# wifi.net
KiCad netlist of a schematic drawn in EAGLE
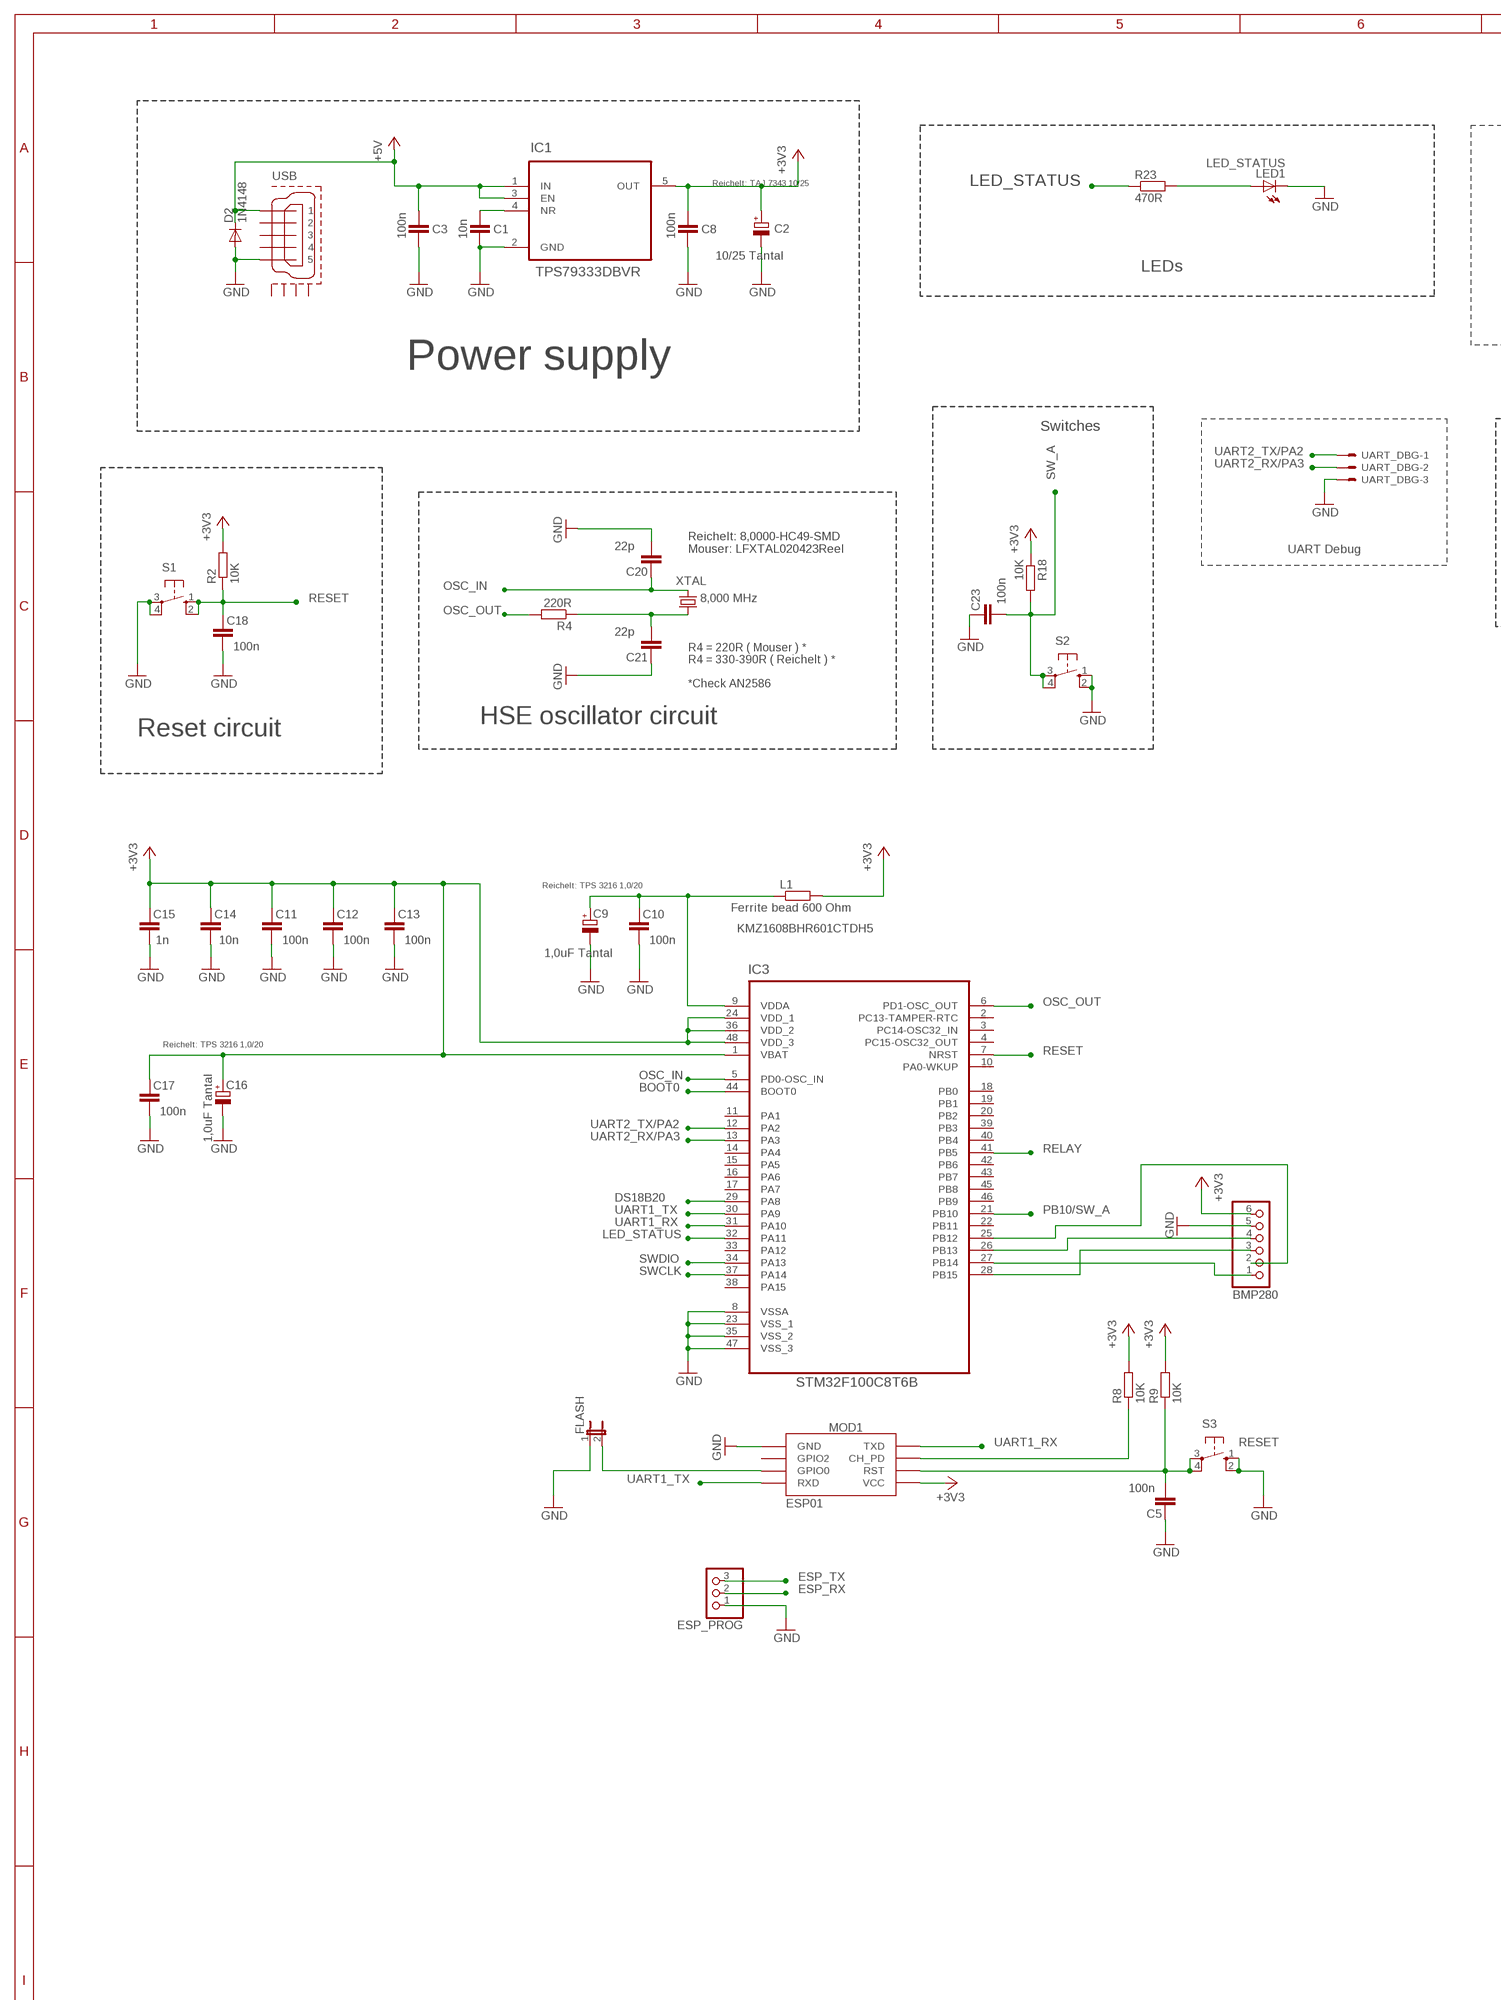
[diagram p0: schematic, sheet 1, part 1 of 2]
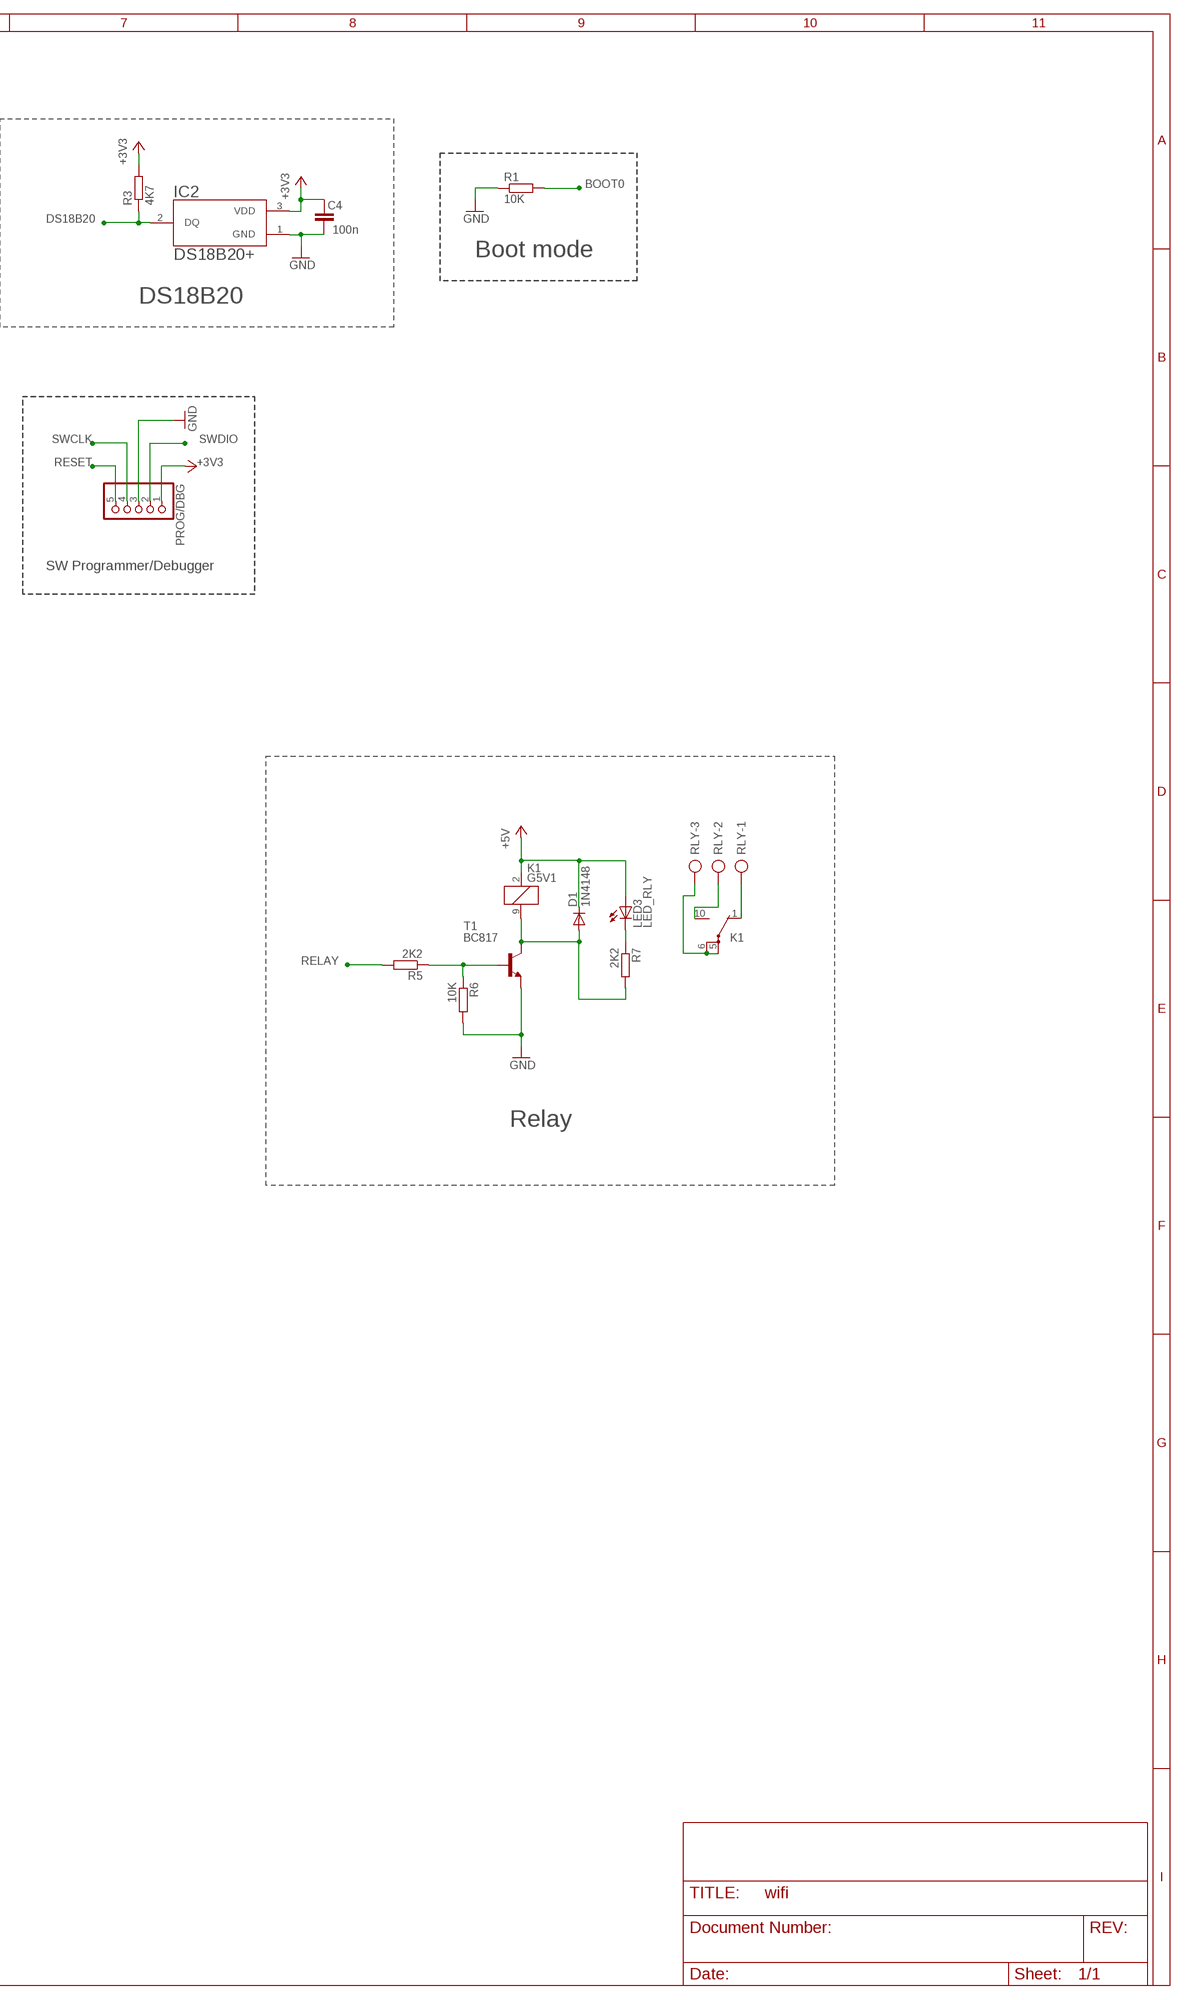
[diagram p1: schematic, sheet 1, part 2 of 2]

(export (version "E")
  (design (tool "Eeschema 10.0.6"))
  (components
    (comp (ref "BMP280")
      (value "PINHD-1X6")
      (footprint "eagle-import:1X06")
      (libsource (lib "eagle-import") (part "PINHD-1X6"))
    )
    (comp (ref "C1")
      (value "10n")
      (footprint "eagle-import:C0805")
      (libsource (lib "eagle-import") (part "C-EUC0805"))
    )
    (comp (ref "C2")
      (value "10/25 Tantal")
      (footprint "eagle-import:SMC_D")
      (libsource (lib "eagle-import") (part "CPOL-EUSMCD"))
    )
    (comp (ref "C3")
      (value "100n")
      (footprint "eagle-import:C0805")
      (libsource (lib "eagle-import") (part "C-EUC0805"))
    )
    (comp (ref "C4")
      (value "100n")
      (footprint "eagle-import:C0805")
      (libsource (lib "eagle-import") (part "C-EUC0805"))
    )
    (comp (ref "C5")
      (value "100n")
      (footprint "eagle-import:C0805")
      (libsource (lib "eagle-import") (part "C-EUC0805"))
    )
    (comp (ref "C8")
      (value "100n")
      (footprint "eagle-import:C0805")
      (libsource (lib "eagle-import") (part "C-EUC0805"))
    )
    (comp (ref "C9")
      (value "1,0uF Tantal")
      (footprint "eagle-import:SMC_A")
      (libsource (lib "eagle-import") (part "CPOL-EUSMCA"))
    )
    (comp (ref "C10")
      (value "100n")
      (footprint "eagle-import:C0402K")
      (libsource (lib "eagle-import") (part "C-EUC0402K"))
    )
    (comp (ref "C11")
      (value "100n")
      (footprint "eagle-import:C0402K")
      (libsource (lib "eagle-import") (part "C-EUC0402K"))
    )
    (comp (ref "C12")
      (value "100n")
      (footprint "eagle-import:C0402K")
      (libsource (lib "eagle-import") (part "C-EUC0402K"))
    )
    (comp (ref "C13")
      (value "100n")
      (footprint "eagle-import:C0402K")
      (libsource (lib "eagle-import") (part "C-EUC0402K"))
    )
    (comp (ref "C14")
      (value "10n")
      (footprint "eagle-import:C0402K")
      (libsource (lib "eagle-import") (part "C-EUC0402K"))
    )
    (comp (ref "C15")
      (value "1n")
      (footprint "eagle-import:C0402K")
      (libsource (lib "eagle-import") (part "C-EUC0402K"))
    )
    (comp (ref "C16")
      (value "1,0uF Tantal")
      (footprint "eagle-import:SMC_A")
      (libsource (lib "eagle-import") (part "CPOL-EUSMCA"))
    )
    (comp (ref "C17")
      (value "100n")
      (footprint "eagle-import:C0402K")
      (libsource (lib "eagle-import") (part "C-EUC0402K"))
    )
    (comp (ref "C18")
      (value "100n")
      (footprint "eagle-import:C0603K")
      (libsource (lib "eagle-import") (part "C-EUC0603K"))
    )
    (comp (ref "C20")
      (value "22p")
      (footprint "eagle-import:C0603K")
      (libsource (lib "eagle-import") (part "C-EUC0603K"))
    )
    (comp (ref "C21")
      (value "22p")
      (footprint "eagle-import:C0603K")
      (libsource (lib "eagle-import") (part "C-EUC0603K"))
    )
    (comp (ref "C23")
      (value "100n")
      (footprint "eagle-import:C0805")
      (libsource (lib "eagle-import") (part "C-EUC0805"))
    )
    (comp (ref "D1")
      (value "1N4148")
      (footprint "eagle-import:DO35-7")
      (libsource (lib "eagle-import") (part "1N4148DO35-7"))
    )
    (comp (ref "D2")
      (value "1N4148")
      (footprint "eagle-import:DO35-7")
      (libsource (lib "eagle-import") (part "1N4148DO35-7"))
    )
    (comp (ref "ESP_PROG")
      (value "PINHD-1X3")
      (footprint "eagle-import:1X03")
      (libsource (lib "eagle-import") (part "PINHD-1X3"))
    )
    (comp (ref "FLASH")
      (value "JP1E")
      (footprint "eagle-import:JP1")
      (libsource (lib "eagle-import") (part "JP1E"))
    )
    (comp (ref "IC1")
      (value "TPS79333DBVR")
      (footprint "eagle-import:SOT95P280X145-5N")
      (fields (field (name "MF") "Texas Instruments"))
      (libsource (lib "eagle-import") (part "TPS79333DBVR"))
    )
    (comp (ref "IC2")
      (value "DS18B20+")
      (footprint "eagle-import:TO-92")
      (fields (field (name "MF") "Maxim Integrated"))
      (libsource (lib "eagle-import") (part "DS18B20+"))
    )
    (comp (ref "IC3")
      (value "STM32F100C8T6B")
      (footprint "eagle-import:QFP50P900X900X160-48N")
      (fields (field (name "MF") "STMicroelectronics"))
      (libsource (lib "eagle-import") (part "STM32F100C8T6B"))
    )
    (comp (ref "K1")
      (value "G5V1")
      (footprint "eagle-import:G5V1")
      (fields (field (name "MPN") "G5V-1-DC24"))
      (libsource (lib "eagle-import") (part "G5V1"))
    )
    (comp (ref "L1")
      (value "Ferrite bead 600 Ohm")
      (footprint "eagle-import:R0603")
      (libsource (lib "eagle-import") (part "R-EU_R0603"))
    )
    (comp (ref "LED1")
      (value "LED_STATUS")
      (footprint "eagle-import:LED3MM")
      (libsource (lib "eagle-import") (part "LED3MM"))
    )
    (comp (ref "LED3")
      (value "LED_RLY")
      (footprint "eagle-import:LED3MM")
      (libsource (lib "eagle-import") (part "LED3MM"))
    )
    (comp (ref "MOD1")
      (value "ESP01")
      (footprint "eagle-import:ESP01")
      (libsource (lib "eagle-import") (part "ESP01"))
    )
    (comp (ref "PROG/DBG")
      (value "PINHD-1X5")
      (footprint "eagle-import:1X05")
      (libsource (lib "eagle-import") (part "PINHD-1X5"))
    )
    (comp (ref "R1")
      (value "10K")
      (footprint "eagle-import:R0805")
      (libsource (lib "eagle-import") (part "R-EU_R0805"))
    )
    (comp (ref "R2")
      (value "10K")
      (footprint "eagle-import:R0603")
      (libsource (lib "eagle-import") (part "R-EU_R0603"))
    )
    (comp (ref "R3")
      (value "4K7")
      (footprint "eagle-import:R0603")
      (libsource (lib "eagle-import") (part "R-EU_R0603"))
    )
    (comp (ref "R4")
      (value "220R")
      (footprint "eagle-import:R0603")
      (libsource (lib "eagle-import") (part "R-EU_R0603"))
    )
    (comp (ref "R5")
      (value "2K2")
      (footprint "eagle-import:R0603")
      (libsource (lib "eagle-import") (part "R-EU_R0603"))
    )
    (comp (ref "R6")
      (value "10K")
      (footprint "eagle-import:R0603")
      (libsource (lib "eagle-import") (part "R-EU_R0603"))
    )
    (comp (ref "R7")
      (value "2K2")
      (footprint "eagle-import:R0805")
      (libsource (lib "eagle-import") (part "R-EU_R0805"))
    )
    (comp (ref "R8")
      (value "10K")
      (footprint "eagle-import:R0603")
      (libsource (lib "eagle-import") (part "R-EU_R0603"))
    )
    (comp (ref "R9")
      (value "10K")
      (footprint "eagle-import:R0603")
      (libsource (lib "eagle-import") (part "R-EU_R0603"))
    )
    (comp (ref "R18")
      (value "10K")
      (footprint "eagle-import:M0805")
      (libsource (lib "eagle-import") (part "R-EU_M0805"))
    )
    (comp (ref "R23")
      (value "470R")
      (footprint "eagle-import:R0805")
      (libsource (lib "eagle-import") (part "R-EU_R0805"))
    )
    (comp (ref "RLY")
      (value "AK300/3")
      (footprint "eagle-import:AK300_3")
      (libsource (lib "eagle-import") (part "AK300/3"))
    )
    (comp (ref "S1")
      (value "10-XX")
      (footprint "eagle-import:B3F-10XX")
      (fields (field (name "MPN") "B3F-1000"))
      (libsource (lib "eagle-import") (part "10-XX"))
    )
    (comp (ref "S2")
      (value "10-XX")
      (footprint "eagle-import:B3F-10XX")
      (fields (field (name "MPN") "B3F-1000"))
      (libsource (lib "eagle-import") (part "10-XX"))
    )
    (comp (ref "S3")
      (value "10-XX")
      (footprint "eagle-import:B3F-10XX")
      (fields (field (name "MPN") "B3F-1000"))
      (libsource (lib "eagle-import") (part "10-XX"))
    )
    (comp (ref "T1")
      (value "BC817")
      (footprint "eagle-import:SOT23-BEC")
      (libsource (lib "eagle-import") (part "BC817SMD-25"))
    )
    (comp (ref "UART_DBG")
      (value "22-23-2031")
      (footprint "eagle-import:22-23-2031")
      (fields (field (name "MF") "MOLEX"))
      (libsource (lib "eagle-import") (part "22-23-2031"))
    )
    (comp (ref "USB")
      (value "MICRO-USB-RECEPTACLE47589-0001")
      (footprint "eagle-import:47589-0001")
      (libsource (lib "eagle-import") (part "MICRO-USB-RECEPTACLE47589-0001"))
    )
    (comp (ref "XTAL")
      (value "8,000 MHz")
      (footprint "eagle-import:SM49")
      (libsource (lib "eagle-import") (part "CRYSTALSM49"))
    )
  )
  (nets
    (net (code "1") (name "+3V3") (class "Default")
      (node (ref "BMP280") (pin "6") (pinfunction "6_6") (pintype "passive"))
      (node (ref "C11") (pin "1") (pinfunction "1_1") (pintype "passive"))
      (node (ref "C12") (pin "1") (pinfunction "1_1") (pintype "passive"))
      (node (ref "C13") (pin "1") (pinfunction "1_1") (pintype "passive"))
      (node (ref "C14") (pin "1") (pinfunction "1_1") (pintype "passive"))
      (node (ref "C15") (pin "1") (pinfunction "1_1") (pintype "passive"))
      (node (ref "C16") (pin "+") (pinfunction "+_+") (pintype "passive"))
      (node (ref "C17") (pin "1") (pinfunction "1_1") (pintype "passive"))
      (node (ref "C2") (pin "+") (pinfunction "+_+") (pintype "passive"))
      (node (ref "C4") (pin "1") (pinfunction "1_1") (pintype "passive"))
      (node (ref "C8") (pin "1") (pinfunction "1_1") (pintype "passive"))
      (node (ref "IC1") (pin "5") (pinfunction "OUT_5") (pintype "output"))
      (node (ref "IC2") (pin "3") (pinfunction "VDD_3") (pintype "power_in"))
      (node (ref "IC3") (pin "1") (pinfunction "VBAT_1") (pintype "power_in"))
      (node (ref "IC3") (pin "24") (pinfunction "VDD_1_24") (pintype "power_in"))
      (node (ref "IC3") (pin "36") (pinfunction "VDD_2_36") (pintype "power_in"))
      (node (ref "IC3") (pin "48") (pinfunction "VDD_3_48") (pintype "power_in"))
      (node (ref "L1") (pin "2") (pinfunction "2_2") (pintype "passive"))
      (node (ref "MOD1") (pin "VCC") (pinfunction "VCC_VCC") (pintype "bidirectional"))
      (node (ref "PROG/DBG") (pin "1") (pinfunction "1_1") (pintype "passive"))
      (node (ref "R18") (pin "1") (pinfunction "1_1") (pintype "passive"))
      (node (ref "R2") (pin "2") (pinfunction "2_2") (pintype "passive"))
      (node (ref "R3") (pin "2") (pinfunction "2_2") (pintype "passive"))
      (node (ref "R8") (pin "2") (pinfunction "2_2") (pintype "passive"))
      (node (ref "R9") (pin "2") (pinfunction "2_2") (pintype "passive"))
    )
    (net (code "2") (name "+5V") (class "Default")
      (node (ref "C3") (pin "1") (pinfunction "1_1") (pintype "passive"))
      (node (ref "D1") (pin "C") (pinfunction "C_C") (pintype "passive"))
      (node (ref "D2") (pin "C") (pinfunction "C_C") (pintype "passive"))
      (node (ref "IC1") (pin "1") (pinfunction "IN_1") (pintype "input"))
      (node (ref "IC1") (pin "3") (pinfunction "EN_3") (pintype "input"))
      (node (ref "K1") (pin "2") (pinfunction "1_2") (pintype "passive"))
      (node (ref "LED3") (pin "A") (pinfunction "A_A") (pintype "passive"))
      (node (ref "USB") (pin "1") (pinfunction "1_1") (pintype "input"))
    )
    (net (code "3") (name "/BOOT0") (class "Default")
      (node (ref "IC3") (pin "44") (pinfunction "BOOT0_44") (pintype "input"))
      (node (ref "R1") (pin "2") (pinfunction "2_2") (pintype "passive"))
    )
    (net (code "4") (name "/DS18B20") (class "Default")
      (node (ref "IC2") (pin "2") (pinfunction "DQ_2") (pintype "bidirectional"))
      (node (ref "IC3") (pin "29") (pinfunction "PA8_29") (pintype "bidirectional"))
      (node (ref "R3") (pin "1") (pinfunction "1_1") (pintype "passive"))
    )
    (net (code "5") (name "/LED_STATUS") (class "Default")
      (node (ref "IC3") (pin "32") (pinfunction "PA11_32") (pintype "bidirectional"))
      (node (ref "R23") (pin "1") (pinfunction "1_1") (pintype "passive"))
    )
    (net (code "6") (name "/OSC_IN") (class "Default")
      (node (ref "C20") (pin "1") (pinfunction "1_1") (pintype "passive"))
      (node (ref "IC3") (pin "5") (pinfunction "PD0-OSC_IN_5") (pintype "input"))
      (node (ref "XTAL") (pin "1") (pinfunction "1_1") (pintype "passive"))
    )
    (net (code "7") (name "/OSC_OUT") (class "Default")
      (node (ref "IC3") (pin "6") (pinfunction "PD1-OSC_OUT_6") (pintype "output"))
      (node (ref "R4") (pin "2") (pinfunction "2_2") (pintype "passive"))
    )
    (net (code "8") (name "/PB10") (class "Default")
      (node (ref "C23") (pin "2") (pinfunction "2_2") (pintype "passive"))
      (node (ref "IC3") (pin "21") (pinfunction "PB10_21") (pintype "bidirectional"))
      (node (ref "R18") (pin "2") (pinfunction "2_2") (pintype "passive"))
      (node (ref "S2") (pin "3") (pinfunction "P_3") (pintype "passive"))
      (node (ref "S2") (pin "4") (pinfunction "P1_4") (pintype "passive"))
    )
    (net (code "9") (name "/RELAY") (class "Default")
      (node (ref "IC3") (pin "41") (pinfunction "PB5_41") (pintype "bidirectional"))
      (node (ref "R5") (pin "2") (pinfunction "2_2") (pintype "passive"))
    )
    (net (code "10") (name "/RESET") (class "Default")
      (node (ref "C18") (pin "1") (pinfunction "1_1") (pintype "passive"))
      (node (ref "IC3") (pin "7") (pinfunction "NRST_7") (pintype "bidirectional"))
      (node (ref "PROG/DBG") (pin "5") (pinfunction "5_5") (pintype "passive"))
      (node (ref "R2") (pin "1") (pinfunction "1_1") (pintype "passive"))
      (node (ref "S1") (pin "1") (pinfunction "S_1") (pintype "passive"))
      (node (ref "S1") (pin "2") (pinfunction "S1_2") (pintype "passive"))
    )
    (net (code "11") (name "/SWCLK") (class "Default")
      (node (ref "IC3") (pin "37") (pinfunction "PA14_37") (pintype "bidirectional"))
      (node (ref "PROG/DBG") (pin "4") (pinfunction "4_4") (pintype "passive"))
    )
    (net (code "12") (name "/SWDIO") (class "Default")
      (node (ref "IC3") (pin "34") (pinfunction "PA13_34") (pintype "bidirectional"))
      (node (ref "PROG/DBG") (pin "2") (pinfunction "2_2") (pintype "passive"))
    )
    (net (code "13") (name "/UART1_RX") (class "Default")
      (node (ref "ESP_PROG") (pin "3") (pinfunction "3_3") (pintype "passive"))
      (node (ref "IC3") (pin "31") (pinfunction "PA10_31") (pintype "bidirectional"))
      (node (ref "MOD1") (pin "TX") (pinfunction "TXD_TX") (pintype "bidirectional"))
    )
    (net (code "14") (name "/UART1_TX") (class "Default")
      (node (ref "ESP_PROG") (pin "2") (pinfunction "2_2") (pintype "passive"))
      (node (ref "IC3") (pin "30") (pinfunction "PA9_30") (pintype "bidirectional"))
      (node (ref "MOD1") (pin "RX") (pinfunction "RXD_RX") (pintype "bidirectional"))
    )
    (net (code "15") (name "/UART2_RX") (class "Default")
      (node (ref "IC3") (pin "13") (pinfunction "PA3_13") (pintype "bidirectional"))
      (node (ref "UART_DBG") (pin "2") (pinfunction "S_2") (pintype "passive"))
    )
    (net (code "16") (name "/UART2_TX") (class "Default")
      (node (ref "IC3") (pin "12") (pinfunction "PA2_12") (pintype "bidirectional"))
      (node (ref "UART_DBG") (pin "1") (pinfunction "S_1") (pintype "passive"))
    )
    (net (code "17") (name "GND") (class "Default")
      (node (ref "BMP280") (pin "5") (pinfunction "5_5") (pintype "passive"))
      (node (ref "C1") (pin "2") (pinfunction "2_2") (pintype "passive"))
      (node (ref "C10") (pin "2") (pinfunction "2_2") (pintype "passive"))
      (node (ref "C11") (pin "2") (pinfunction "2_2") (pintype "passive"))
      (node (ref "C12") (pin "2") (pinfunction "2_2") (pintype "passive"))
      (node (ref "C13") (pin "2") (pinfunction "2_2") (pintype "passive"))
      (node (ref "C14") (pin "2") (pinfunction "2_2") (pintype "passive"))
      (node (ref "C15") (pin "2") (pinfunction "2_2") (pintype "passive"))
      (node (ref "C16") (pin "-") (pinfunction "-_-") (pintype "passive"))
      (node (ref "C17") (pin "2") (pinfunction "2_2") (pintype "passive"))
      (node (ref "C18") (pin "2") (pinfunction "2_2") (pintype "passive"))
      (node (ref "C2") (pin "-") (pinfunction "-_-") (pintype "passive"))
      (node (ref "C20") (pin "2") (pinfunction "2_2") (pintype "passive"))
      (node (ref "C21") (pin "1") (pinfunction "1_1") (pintype "passive"))
      (node (ref "C23") (pin "1") (pinfunction "1_1") (pintype "passive"))
      (node (ref "C3") (pin "2") (pinfunction "2_2") (pintype "passive"))
      (node (ref "C4") (pin "2") (pinfunction "2_2") (pintype "passive"))
      (node (ref "C5") (pin "1") (pinfunction "1_1") (pintype "passive"))
      (node (ref "C8") (pin "2") (pinfunction "2_2") (pintype "passive"))
      (node (ref "C9") (pin "-") (pinfunction "-_-") (pintype "passive"))
      (node (ref "D2") (pin "A") (pinfunction "A_A") (pintype "passive"))
      (node (ref "ESP_PROG") (pin "1") (pinfunction "1_1") (pintype "passive"))
      (node (ref "FLASH") (pin "1") (pinfunction "1_1") (pintype "passive"))
      (node (ref "IC1") (pin "2") (pinfunction "GND_2") (pintype "input"))
      (node (ref "IC2") (pin "1") (pinfunction "GND_1") (pintype "power_in"))
      (node (ref "IC3") (pin "23") (pinfunction "VSS_1_23") (pintype "power_in"))
      (node (ref "IC3") (pin "35") (pinfunction "VSS_2_35") (pintype "power_in"))
      (node (ref "IC3") (pin "47") (pinfunction "VSS_3_47") (pintype "power_in"))
      (node (ref "IC3") (pin "8") (pinfunction "VSSA_8") (pintype "power_in"))
      (node (ref "LED1") (pin "K") (pinfunction "C_K") (pintype "passive"))
      (node (ref "MOD1") (pin "GND") (pinfunction "GND_GND") (pintype "bidirectional"))
      (node (ref "PROG/DBG") (pin "3") (pinfunction "3_3") (pintype "passive"))
      (node (ref "R1") (pin "1") (pinfunction "1_1") (pintype "passive"))
      (node (ref "R6") (pin "2") (pinfunction "2_2") (pintype "passive"))
      (node (ref "S1") (pin "3") (pinfunction "P_3") (pintype "passive"))
      (node (ref "S1") (pin "4") (pinfunction "P1_4") (pintype "passive"))
      (node (ref "S2") (pin "1") (pinfunction "S_1") (pintype "passive"))
      (node (ref "S2") (pin "2") (pinfunction "S1_2") (pintype "passive"))
      (node (ref "S3") (pin "1") (pinfunction "S_1") (pintype "passive"))
      (node (ref "S3") (pin "2") (pinfunction "S1_2") (pintype "passive"))
      (node (ref "T1") (pin "E") (pinfunction "E_E") (pintype "passive"))
      (node (ref "UART_DBG") (pin "3") (pinfunction "S_3") (pintype "passive"))
      (node (ref "USB") (pin "5") (pinfunction "5_5") (pintype "input"))
    )
    (net (code "18") (name "Net-(C21-Pad2)") (class "Default")
      (node (ref "C21") (pin "2") (pinfunction "2_2") (pintype "passive"))
      (node (ref "R4") (pin "1") (pinfunction "1_1") (pintype "passive"))
      (node (ref "XTAL") (pin "2") (pinfunction "2_2") (pintype "passive"))
    )
    (net (code "19") (name "Net-(FLASH-Pad2)") (class "Default")
      (node (ref "FLASH") (pin "2") (pinfunction "2_2") (pintype "passive"))
      (node (ref "MOD1") (pin "GPIO0") (pinfunction "GPIO0_GPIO0") (pintype "bidirectional"))
    )
    (net (code "20") (name "Net-(IC1-NR)") (class "Default")
      (node (ref "C1") (pin "1") (pinfunction "1_1") (pintype "passive"))
      (node (ref "IC1") (pin "4") (pinfunction "NR_4") (pintype "input"))
    )
    (net (code "21") (name "Net-(IC3-PB12)") (class "Default")
      (node (ref "BMP280") (pin "2") (pinfunction "2_2") (pintype "passive"))
      (node (ref "IC3") (pin "25") (pinfunction "PB12_25") (pintype "bidirectional"))
    )
    (net (code "22") (name "Net-(IC3-PB13)") (class "Default")
      (node (ref "BMP280") (pin "4") (pinfunction "4_4") (pintype "passive"))
      (node (ref "IC3") (pin "26") (pinfunction "PB13_26") (pintype "bidirectional"))
    )
    (net (code "23") (name "Net-(IC3-PB14)") (class "Default")
      (node (ref "BMP280") (pin "1") (pinfunction "1_1") (pintype "passive"))
      (node (ref "IC3") (pin "27") (pinfunction "PB14_27") (pintype "bidirectional"))
    )
    (net (code "24") (name "Net-(IC3-PB15)") (class "Default")
      (node (ref "BMP280") (pin "3") (pinfunction "3_3") (pintype "passive"))
      (node (ref "IC3") (pin "28") (pinfunction "PB15_28") (pintype "bidirectional"))
    )
    (net (code "25") (name "Net-(IC3-VDDA)") (class "Default")
      (node (ref "C10") (pin "1") (pinfunction "1_1") (pintype "passive"))
      (node (ref "C9") (pin "+") (pinfunction "+_+") (pintype "passive"))
      (node (ref "IC3") (pin "9") (pinfunction "VDDA_9") (pintype "power_in"))
      (node (ref "L1") (pin "1") (pinfunction "1_1") (pintype "passive"))
    )
    (net (code "26") (name "Net-(K1A-2)") (class "Default")
      (node (ref "D1") (pin "A") (pinfunction "A_A") (pintype "passive"))
      (node (ref "K1") (pin "9") (pinfunction "2_9") (pintype "passive"))
      (node (ref "R7") (pin "2") (pinfunction "2_2") (pintype "passive"))
      (node (ref "T1") (pin "C") (pinfunction "C_C") (pintype "passive"))
    )
    (net (code "27") (name "Net-(K1B-O)") (class "Default")
      (node (ref "K1") (pin "1") (pinfunction "O_1") (pintype "passive"))
      (node (ref "RLY") (pin "1") (pinfunction "KL_1") (pintype "passive"))
    )
    (net (code "28") (name "Net-(K1B-S)") (class "Default")
      (node (ref "K1") (pin "10") (pinfunction "S_10") (pintype "passive"))
      (node (ref "RLY") (pin "2") (pinfunction "KL_2") (pintype "passive"))
    )
    (net (code "29") (name "Net-(LED1-PadA)") (class "Default")
      (node (ref "LED1") (pin "A") (pinfunction "A_A") (pintype "passive"))
      (node (ref "R23") (pin "2") (pinfunction "2_2") (pintype "passive"))
    )
    (net (code "30") (name "Net-(LED3-C)") (class "Default")
      (node (ref "LED3") (pin "K") (pinfunction "C_K") (pintype "passive"))
      (node (ref "R7") (pin "1") (pinfunction "1_1") (pintype "passive"))
    )
    (net (code "31") (name "Net-(MOD1-PadCH_PD)") (class "Default")
      (node (ref "MOD1") (pin "CH_PD") (pinfunction "CH_PD_CH_PD") (pintype "bidirectional"))
      (node (ref "R8") (pin "1") (pinfunction "1_1") (pintype "passive"))
    )
    (net (code "32") (name "Net-(R5-Pad1)") (class "Default")
      (node (ref "R5") (pin "1") (pinfunction "1_1") (pintype "passive"))
      (node (ref "R6") (pin "1") (pinfunction "1_1") (pintype "passive"))
      (node (ref "T1") (pin "B") (pinfunction "B_B") (pintype "passive"))
    )
    (net (code "33") (name "Net-(RLYC-KL)") (class "Default")
      (node (ref "K1") (pin "5") (pinfunction "P_5") (pintype "passive"))
      (node (ref "K1") (pin "6") (pinfunction "P_6") (pintype "passive"))
      (node (ref "RLY") (pin "3") (pinfunction "KL_3") (pintype "passive"))
    )
    (net (code "34") (name "Net-(S3-P)") (class "Default")
      (node (ref "C5") (pin "2") (pinfunction "2_2") (pintype "passive"))
      (node (ref "MOD1") (pin "RST") (pinfunction "RST_RST") (pintype "bidirectional"))
      (node (ref "R9") (pin "1") (pinfunction "1_1") (pintype "passive"))
      (node (ref "S3") (pin "3") (pinfunction "P_3") (pintype "passive"))
      (node (ref "S3") (pin "4") (pinfunction "P1_4") (pintype "passive"))
    )
    (net (code "35") (name "unconnected-(IC3-PA0-WKUP-Pad10)") (class "Default")
      (node (ref "IC3") (pin "10") (pinfunction "PA0-WKUP_10") (pintype "bidirectional"))
    )
    (net (code "36") (name "unconnected-(IC3-PA1-Pad11)") (class "Default")
      (node (ref "IC3") (pin "11") (pinfunction "PA1_11") (pintype "bidirectional"))
    )
    (net (code "37") (name "unconnected-(IC3-PA4-Pad14)") (class "Default")
      (node (ref "IC3") (pin "14") (pinfunction "PA4_14") (pintype "bidirectional"))
    )
    (net (code "38") (name "unconnected-(IC3-PA5-Pad15)") (class "Default")
      (node (ref "IC3") (pin "15") (pinfunction "PA5_15") (pintype "bidirectional"))
    )
    (net (code "39") (name "unconnected-(IC3-PA6-Pad16)") (class "Default")
      (node (ref "IC3") (pin "16") (pinfunction "PA6_16") (pintype "bidirectional"))
    )
    (net (code "40") (name "unconnected-(IC3-PA7-Pad17)") (class "Default")
      (node (ref "IC3") (pin "17") (pinfunction "PA7_17") (pintype "bidirectional"))
    )
    (net (code "41") (name "unconnected-(IC3-PA12-Pad33)") (class "Default")
      (node (ref "IC3") (pin "33") (pinfunction "PA12_33") (pintype "bidirectional"))
    )
    (net (code "42") (name "unconnected-(IC3-PA15-Pad38)") (class "Default")
      (node (ref "IC3") (pin "38") (pinfunction "PA15_38") (pintype "bidirectional"))
    )
    (net (code "43") (name "unconnected-(IC3-PB0-Pad18)") (class "Default")
      (node (ref "IC3") (pin "18") (pinfunction "PB0_18") (pintype "bidirectional"))
    )
    (net (code "44") (name "unconnected-(IC3-PB1-Pad19)") (class "Default")
      (node (ref "IC3") (pin "19") (pinfunction "PB1_19") (pintype "bidirectional"))
    )
    (net (code "45") (name "unconnected-(IC3-PB2-Pad20)") (class "Default")
      (node (ref "IC3") (pin "20") (pinfunction "PB2_20") (pintype "bidirectional"))
    )
    (net (code "46") (name "unconnected-(IC3-PB3-Pad39)") (class "Default")
      (node (ref "IC3") (pin "39") (pinfunction "PB3_39") (pintype "bidirectional"))
    )
    (net (code "47") (name "unconnected-(IC3-PB4-Pad40)") (class "Default")
      (node (ref "IC3") (pin "40") (pinfunction "PB4_40") (pintype "bidirectional"))
    )
    (net (code "48") (name "unconnected-(IC3-PB6-Pad42)") (class "Default")
      (node (ref "IC3") (pin "42") (pinfunction "PB6_42") (pintype "bidirectional"))
    )
    (net (code "49") (name "unconnected-(IC3-PB7-Pad43)") (class "Default")
      (node (ref "IC3") (pin "43") (pinfunction "PB7_43") (pintype "bidirectional"))
    )
    (net (code "50") (name "unconnected-(IC3-PB8-Pad45)") (class "Default")
      (node (ref "IC3") (pin "45") (pinfunction "PB8_45") (pintype "bidirectional"))
    )
    (net (code "51") (name "unconnected-(IC3-PB9-Pad46)") (class "Default")
      (node (ref "IC3") (pin "46") (pinfunction "PB9_46") (pintype "bidirectional"))
    )
    (net (code "52") (name "unconnected-(IC3-PB11-Pad22)") (class "Default")
      (node (ref "IC3") (pin "22") (pinfunction "PB11_22") (pintype "bidirectional"))
    )
    (net (code "53") (name "unconnected-(IC3-PC13-TAMPER-RTC-Pad2)") (class "Default")
      (node (ref "IC3") (pin "2") (pinfunction "PC13-TAMPER-RTC_2") (pintype "bidirectional"))
    )
    (net (code "54") (name "unconnected-(IC3-PC14-OSC32_IN-Pad3)") (class "Default")
      (node (ref "IC3") (pin "3") (pinfunction "PC14-OSC32_IN_3") (pintype "bidirectional"))
    )
    (net (code "55") (name "unconnected-(IC3-PC15-OSC32_OUT-Pad4)") (class "Default")
      (node (ref "IC3") (pin "4") (pinfunction "PC15-OSC32_OUT_4") (pintype "bidirectional"))
    )
    (net (code "56") (name "unconnected-(MOD1-PadGPIO2)") (class "Default")
      (node (ref "MOD1") (pin "GPIO2") (pinfunction "GPIO2_GPIO2") (pintype "bidirectional"))
    )
    (net (code "57") (name "unconnected-(USB-GND1-PadCASING1)") (class "Default")
      (node (ref "USB") (pin "CASING1") (pinfunction "GND1_CASING1") (pintype "bidirectional"))
    )
    (net (code "58") (name "unconnected-(USB-GND2-PadCASING2)") (class "Default")
      (node (ref "USB") (pin "CASING2") (pinfunction "GND2_CASING2") (pintype "bidirectional"))
    )
    (net (code "59") (name "unconnected-(USB-GND3-PadCASING3)") (class "Default")
      (node (ref "USB") (pin "CASING3") (pinfunction "GND3_CASING3") (pintype "bidirectional"))
    )
    (net (code "60") (name "unconnected-(USB-GND4-PadCASING4)") (class "Default")
      (node (ref "USB") (pin "CASING4") (pinfunction "GND4_CASING4") (pintype "bidirectional"))
    )
    (net (code "61") (name "unconnected-(USB-Pad2)") (class "Default")
      (node (ref "USB") (pin "2") (pinfunction "2_2") (pintype "input"))
    )
    (net (code "62") (name "unconnected-(USB-Pad3)") (class "Default")
      (node (ref "USB") (pin "3") (pinfunction "3_3") (pintype "input"))
    )
    (net (code "63") (name "unconnected-(USB-Pad4)") (class "Default")
      (node (ref "USB") (pin "4") (pinfunction "4_4") (pintype "input"))
    )
  )
)
